# Sheet4.net
KiCad netlist of a schematic drawn in Altium Designer
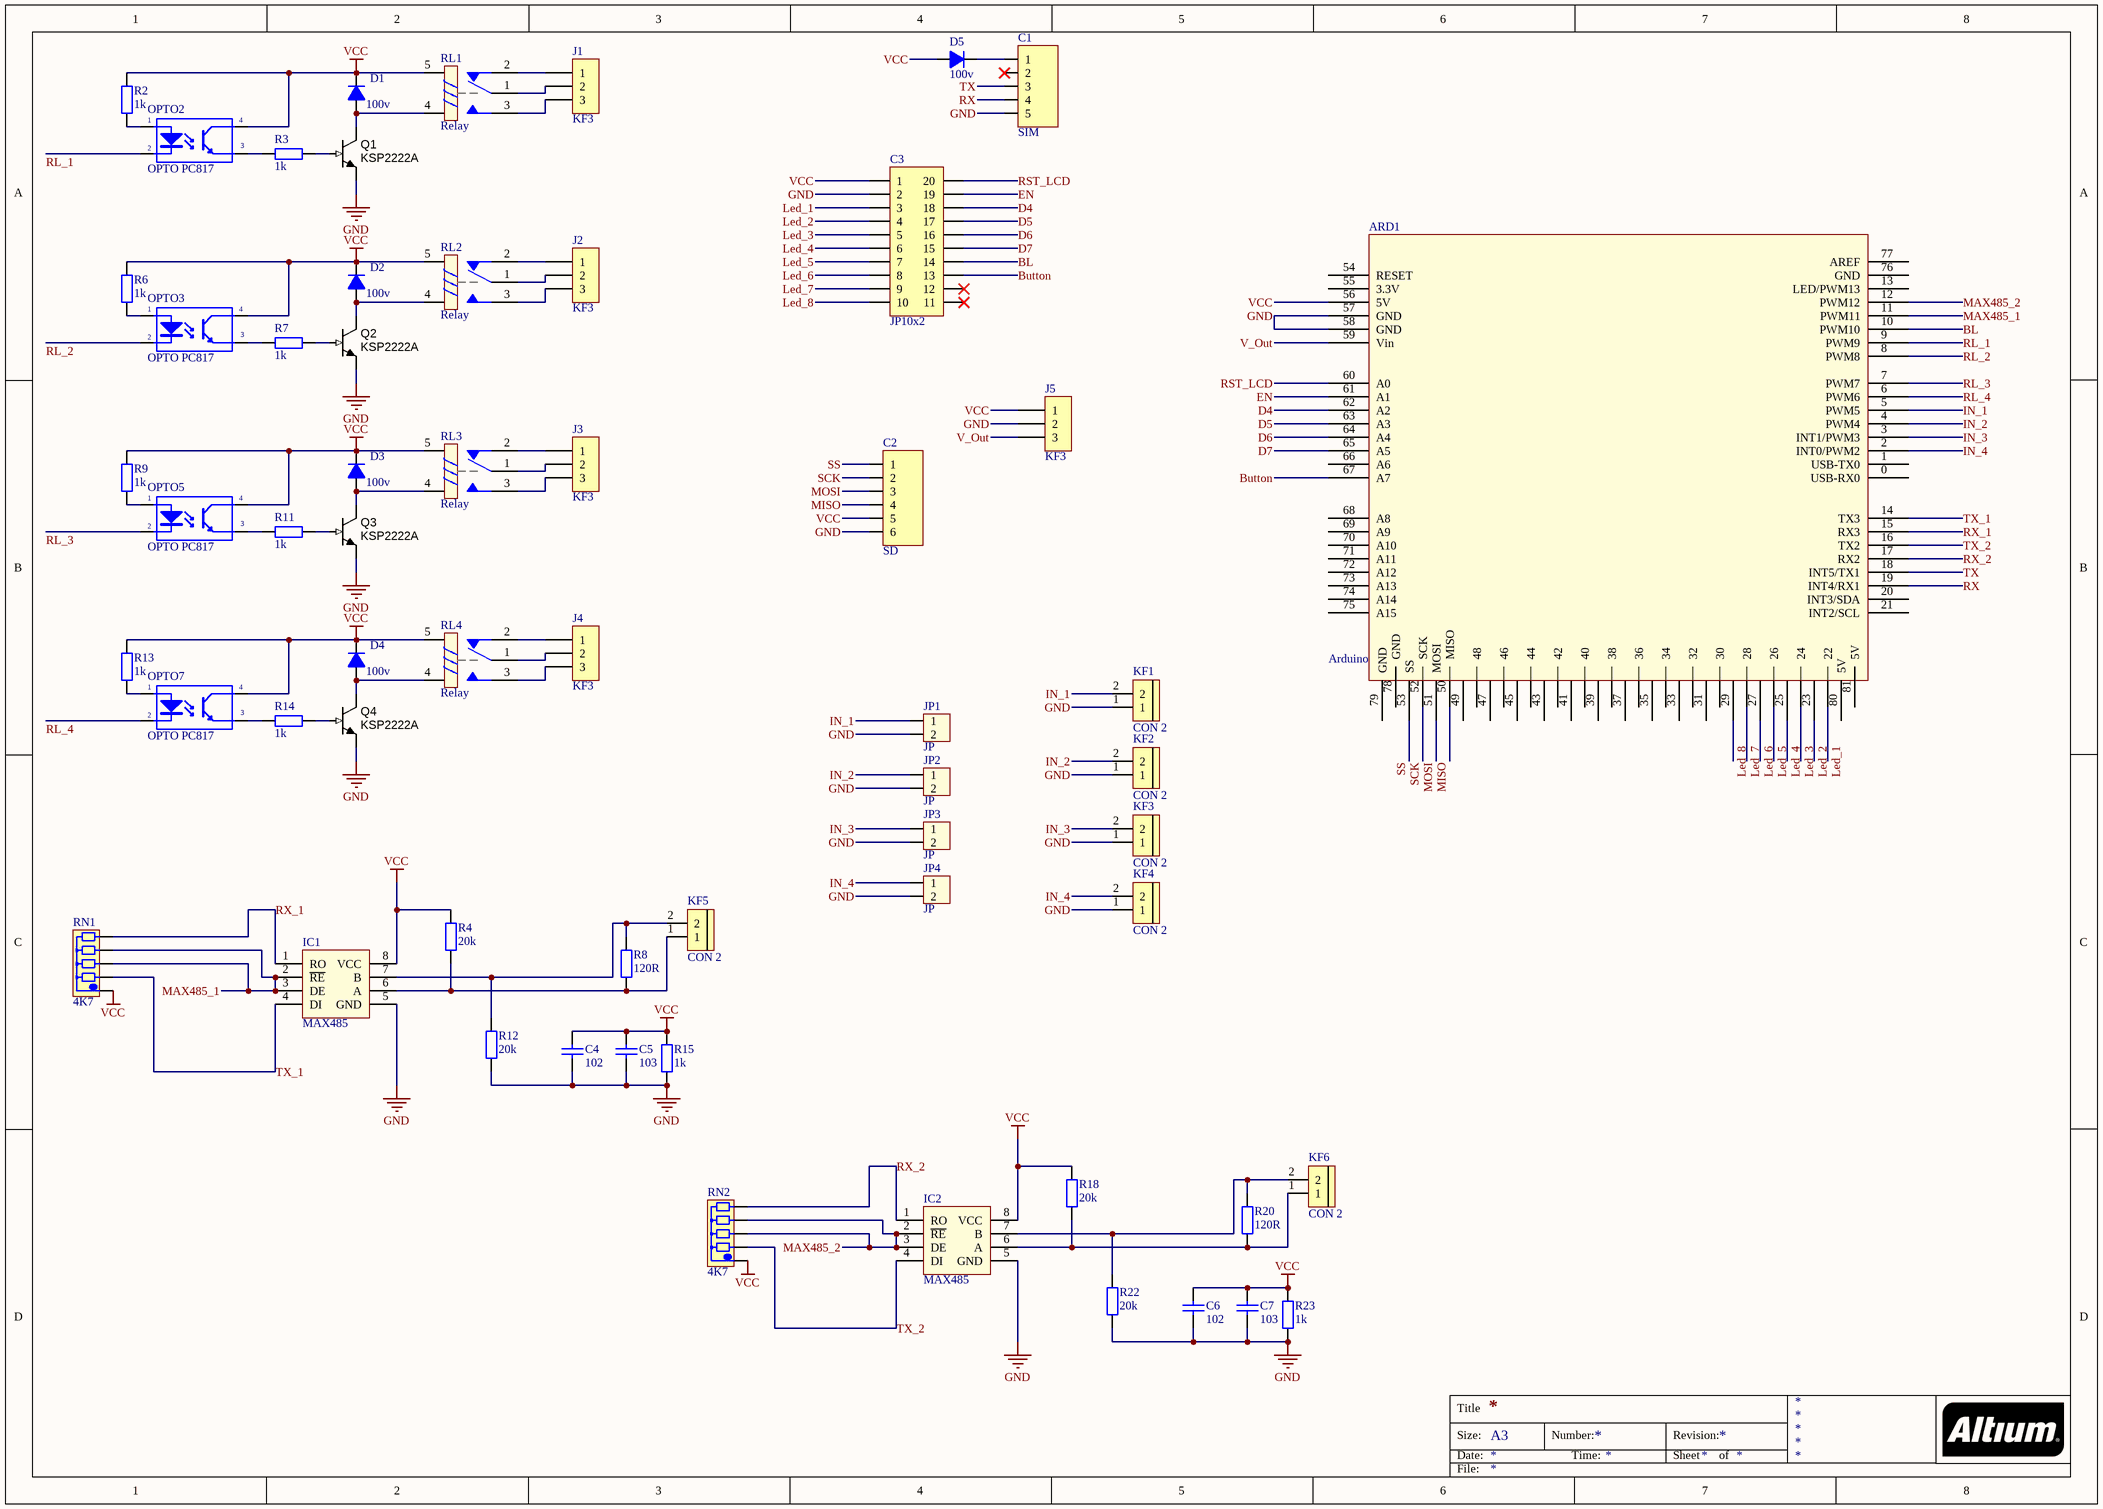
[diagram p0: Sheet4.SchDoc]

(export (version "E")
  (design (tool "Eeschema 10.0.6"))
  (components
    (comp (ref "ARD1") (value "Arduino") (footprint "Arduino") (libsource (lib "Arduino") (part "Arduino")))
    (comp (ref "C1")
      (value "SIM")
      (footprint "JP5-C1T")
      (description "WR-PHD 2.54 mm Angled Socket Header")
      (fields
        (field (name "MANUFACTURER") "Würth Elektronik eiSos GmbH")
        (field (name "PARTNO") "613005143121")
        (field (name "CREATED BY") "Karrer Zheng")
      )
      (libsource (lib "LIBRARY") (part "JP5"))
    )
    (comp (ref "C2")
      (value "SD")
      (footprint "JP6-C1T")
      (description "WR-PHD 2.54 mm Angled Socket Header")
      (fields
        (field (name "MANUFACTURER") "Würth Elektronik eiSos GmbH")
        (field (name "PARTNO") "613006143121")
        (field (name "CREATED BY") "Karrer Zheng")
      )
      (libsource (lib "LIBRARY") (part "JP6"))
    )
    (comp (ref "C3")
      (value "JP10x2")
      (footprint "JP10-C2T")
      (description "WR-PHD 2.54 mm Dual Socket Header")
      (fields
        (field (name "MANUFACTURER") "Würth Elektronik eiSos GmbH")
        (field (name "PARTNO") "61302021821")
        (field (name "CREATED BY") "Karrer Zheng")
      )
      (libsource (lib "LIBRARY") (part "JP10x2"))
    )
    (comp (ref "C4")
      (value "102")
      (footprint "tu gom")
      (description "Cắm")
      (libsource (lib "Altium_Lib_by_KhueNguyenCreator") (part "Tu gom 102 50V"))
    )
    (comp (ref "C5")
      (value "103")
      (footprint "tu gom")
      (description "Cắm")
      (libsource (lib "Altium_Lib_by_KhueNguyenCreator") (part "Tu gom 103 50V"))
    )
    (comp (ref "C6")
      (value "102")
      (footprint "tu gom")
      (description "Cắm")
      (libsource (lib "Altium_Lib_by_KhueNguyenCreator") (part "Tu gom 102 50V"))
    )
    (comp (ref "C7")
      (value "103")
      (footprint "tu gom")
      (description "Cắm")
      (libsource (lib "Altium_Lib_by_KhueNguyenCreator") (part "Tu gom 103 50V"))
    )
    (comp (ref "D1")
      (value "100v")
      (footprint "DIODE 1A")
      (description "Cắm")
      (libsource (lib "Altium_Lib_by_KhueNguyenCreator") (part "Diode 1N4007"))
    )
    (comp (ref "D2")
      (value "100v")
      (footprint "DIODE 1A")
      (description "Cắm")
      (libsource (lib "Altium_Lib_by_KhueNguyenCreator") (part "Diode 1N4007"))
    )
    (comp (ref "D3")
      (value "100v")
      (footprint "DIODE 1A")
      (description "Cắm")
      (libsource (lib "Altium_Lib_by_KhueNguyenCreator") (part "Diode 1N4007"))
    )
    (comp (ref "D4")
      (value "100v")
      (footprint "DIODE 1A")
      (description "Cắm")
      (libsource (lib "Altium_Lib_by_KhueNguyenCreator") (part "Diode 1N4007"))
    )
    (comp (ref "D5")
      (value "100v")
      (footprint "DIODE 1A")
      (description "Cắm")
      (libsource (lib "Altium_Lib_by_KhueNguyenCreator") (part "Diode 1N4007"))
    )
    (comp (ref "IC1")
      (value "MAX485")
      (footprint "DIP8/W0.3")
      (description "RS232 - RS485 (Same sn75176)")
      (libsource (lib "My Library") (part "MAX485"))
    )
    (comp (ref "IC2")
      (value "MAX485")
      (footprint "DIP8/W0.3")
      (description "RS232 - RS485 (Same sn75176)")
      (libsource (lib "My Library") (part "MAX485"))
    )
    (comp (ref "J1")
      (value "KF3")
      (footprint "KF3-5.08")
      (fields
        (field (name "MANUFACTURER") "Würth Elektronik eiSos GmbH")
        (field (name "PARTNO") "691103110003")
        (field (name "CREATED BY") "Karrer Zheng")
      )
      (libsource (lib "My Library") (part "KF3"))
    )
    (comp (ref "J2")
      (value "KF3")
      (footprint "KF3-5.08")
      (fields
        (field (name "MANUFACTURER") "Würth Elektronik eiSos GmbH")
        (field (name "PARTNO") "691103110003")
        (field (name "CREATED BY") "Karrer Zheng")
      )
      (libsource (lib "My Library") (part "KF3"))
    )
    (comp (ref "J3")
      (value "KF3")
      (footprint "KF3-5.08")
      (fields
        (field (name "MANUFACTURER") "Würth Elektronik eiSos GmbH")
        (field (name "PARTNO") "691103110003")
        (field (name "CREATED BY") "Karrer Zheng")
      )
      (libsource (lib "My Library") (part "KF3"))
    )
    (comp (ref "J4")
      (value "KF3")
      (footprint "KF3-5.08")
      (fields
        (field (name "MANUFACTURER") "Würth Elektronik eiSos GmbH")
        (field (name "PARTNO") "691103110003")
        (field (name "CREATED BY") "Karrer Zheng")
      )
      (libsource (lib "My Library") (part "KF3"))
    )
    (comp (ref "J5")
      (value "KF3")
      (footprint "KF3-5.08")
      (fields
        (field (name "MANUFACTURER") "Würth Elektronik eiSos GmbH")
        (field (name "PARTNO") "691103110003")
        (field (name "CREATED BY") "Karrer Zheng")
      )
      (libsource (lib "My Library") (part "KF3"))
    )
    (comp (ref "JP1")
      (value "JP")
      (footprint "jam2")
      (description "jam 2")
      (libsource (lib "My_Library_Altium") (part "Jam 2"))
    )
    (comp (ref "JP2")
      (value "JP")
      (footprint "jam2")
      (description "jam 2")
      (libsource (lib "My_Library_Altium") (part "Jam 2"))
    )
    (comp (ref "JP3")
      (value "JP")
      (footprint "jam2")
      (description "jam 2")
      (libsource (lib "My_Library_Altium") (part "Jam 2"))
    )
    (comp (ref "JP4")
      (value "JP")
      (footprint "jam2")
      (description "jam 2")
      (libsource (lib "My_Library_Altium") (part "Jam 2"))
    )
    (comp (ref "KF1")
      (value "CON 2")
      (footprint "Con 2 KF301 5.08")
      (description "Cắm")
      (libsource (lib "Altium_Lib_by_KhueNguyenCreator") (part "CON 2 KF301"))
    )
    (comp (ref "KF2")
      (value "CON 2")
      (footprint "Con 2 KF301 5.08")
      (description "Cắm")
      (libsource (lib "Altium_Lib_by_KhueNguyenCreator") (part "CON 2 KF301"))
    )
    (comp (ref "KF3")
      (value "CON 2")
      (footprint "Con 2 KF301 5.08")
      (description "Cắm")
      (libsource (lib "Altium_Lib_by_KhueNguyenCreator") (part "CON 2 KF301"))
    )
    (comp (ref "KF4")
      (value "CON 2")
      (footprint "Con 2 KF301 5.08")
      (description "Cắm")
      (libsource (lib "Altium_Lib_by_KhueNguyenCreator") (part "CON 2 KF301"))
    )
    (comp (ref "KF5")
      (value "CON 2")
      (footprint "Con 2 KF301 5.08")
      (description "Cắm")
      (libsource (lib "Altium_Lib_by_KhueNguyenCreator") (part "CON 2 KF301"))
    )
    (comp (ref "KF6")
      (value "CON 2")
      (footprint "Con 2 KF301 5.08")
      (description "Cắm")
      (libsource (lib "Altium_Lib_by_KhueNguyenCreator") (part "CON 2 KF301"))
    )
    (comp (ref "OPTO2")
      (value "OPTO PC817")
      (footprint "DIP4/W0.3")
      (description "Single Opto")
      (libsource (lib "My_Library_Altium") (part "OPTO PC817"))
    )
    (comp (ref "OPTO3")
      (value "OPTO PC817")
      (footprint "DIP4/W0.3")
      (description "Single Opto")
      (libsource (lib "My_Library_Altium") (part "OPTO PC817"))
    )
    (comp (ref "OPTO5")
      (value "OPTO PC817")
      (footprint "DIP4/W0.3")
      (description "Single Opto")
      (libsource (lib "My_Library_Altium") (part "OPTO PC817"))
    )
    (comp (ref "OPTO7")
      (value "OPTO PC817")
      (footprint "DIP4/W0.3")
      (description "Single Opto")
      (libsource (lib "My_Library_Altium") (part "OPTO PC817"))
    )
    (comp (ref "Q1")
      (value "KSP2222A")
      (footprint "TO-92_Flat")
      (description "Transistor SMD NPN 40V 0.6A 625mW TO-92")
      (libsource (lib "My_Library_Altium") (part "NPN_KSP2222A"))
    )
    (comp (ref "Q2")
      (value "KSP2222A")
      (footprint "TO-92_Flat")
      (description "Transistor SMD NPN 40V 0.6A 625mW TO-92")
      (libsource (lib "My_Library_Altium") (part "NPN_KSP2222A"))
    )
    (comp (ref "Q3")
      (value "KSP2222A")
      (footprint "TO-92_Flat")
      (description "Transistor SMD NPN 40V 0.6A 625mW TO-92")
      (libsource (lib "My_Library_Altium") (part "NPN_KSP2222A"))
    )
    (comp (ref "Q4")
      (value "KSP2222A")
      (footprint "TO-92_Flat")
      (description "Transistor SMD NPN 40V 0.6A 625mW TO-92")
      (libsource (lib "My_Library_Altium") (part "NPN_KSP2222A"))
    )
    (comp (ref "R2")
      (value "1k")
      (footprint "tro vach 1/2w")
      (description "Cắm")
      (libsource (lib "Altium_Lib_by_KhueNguyenCreator") (part "Tro Vach 1/2W 5% 1k"))
    )
    (comp (ref "R3")
      (value "1k")
      (footprint "tro vach 1/2w")
      (description "Cắm")
      (libsource (lib "Altium_Lib_by_KhueNguyenCreator") (part "Tro Vach 1/2W 5% 1k"))
    )
    (comp (ref "R4")
      (value "20k")
      (footprint "tro vach 1/4w")
      (description "Cắm")
      (libsource (lib "Altium_Lib_by_KhueNguyenCreator") (part "Tro Vach 1/4W 5% 20k"))
    )
    (comp (ref "R6")
      (value "1k")
      (footprint "tro vach 1/2w")
      (description "Cắm")
      (libsource (lib "Altium_Lib_by_KhueNguyenCreator") (part "Tro Vach 1/2W 5% 1k"))
    )
    (comp (ref "R7")
      (value "1k")
      (footprint "tro vach 1/2w")
      (description "Cắm")
      (libsource (lib "Altium_Lib_by_KhueNguyenCreator") (part "Tro Vach 1/2W 5% 1k"))
    )
    (comp (ref "R8")
      (value "120R")
      (footprint "tro vach 1/4w")
      (description "Cắm")
      (libsource (lib "Altium_Lib_by_KhueNguyenCreator") (part "Tro Vach 1/4W 5% 120R"))
    )
    (comp (ref "R9")
      (value "1k")
      (footprint "tro vach 1/2w")
      (description "Cắm")
      (libsource (lib "Altium_Lib_by_KhueNguyenCreator") (part "Tro Vach 1/2W 5% 1k"))
    )
    (comp (ref "R11")
      (value "1k")
      (footprint "tro vach 1/2w")
      (description "Cắm")
      (libsource (lib "Altium_Lib_by_KhueNguyenCreator") (part "Tro Vach 1/2W 5% 1k"))
    )
    (comp (ref "R12")
      (value "20k")
      (footprint "tro vach 1/4w")
      (description "Cắm")
      (libsource (lib "Altium_Lib_by_KhueNguyenCreator") (part "Tro Vach 1/4W 5% 20k"))
    )
    (comp (ref "R13")
      (value "1k")
      (footprint "tro vach 1/2w")
      (description "Cắm")
      (libsource (lib "Altium_Lib_by_KhueNguyenCreator") (part "Tro Vach 1/2W 5% 1k"))
    )
    (comp (ref "R14")
      (value "1k")
      (footprint "tro vach 1/2w")
      (description "Cắm")
      (libsource (lib "Altium_Lib_by_KhueNguyenCreator") (part "Tro Vach 1/2W 5% 1k"))
    )
    (comp (ref "R15")
      (value "1k")
      (footprint "tro vach 1/4w")
      (description "Cắm")
      (libsource (lib "Altium_Lib_by_KhueNguyenCreator") (part "Tro Vach 1/4W 5% 1k"))
    )
    (comp (ref "R18")
      (value "20k")
      (footprint "tro vach 1/4w")
      (description "Cắm")
      (libsource (lib "Altium_Lib_by_KhueNguyenCreator") (part "Tro Vach 1/4W 5% 20k"))
    )
    (comp (ref "R20")
      (value "120R")
      (footprint "tro vach 1/4w")
      (description "Cắm")
      (libsource (lib "Altium_Lib_by_KhueNguyenCreator") (part "Tro Vach 1/4W 5% 120R"))
    )
    (comp (ref "R22")
      (value "20k")
      (footprint "tro vach 1/4w")
      (description "Cắm")
      (libsource (lib "Altium_Lib_by_KhueNguyenCreator") (part "Tro Vach 1/4W 5% 20k"))
    )
    (comp (ref "R23")
      (value "1k")
      (footprint "tro vach 1/4w")
      (description "Cắm")
      (libsource (lib "Altium_Lib_by_KhueNguyenCreator") (part "Tro Vach 1/4W 5% 1k"))
    )
    (comp (ref "RL1")
      (value "Relay")
      (footprint "Relay 5 Chan SRD")
      (description "Relay 5 Chan")
      (libsource (lib "Altium_Lib_by_KhueNguyenCreator") (part "Relay 5 Chan SRD"))
    )
    (comp (ref "RL2")
      (value "Relay")
      (footprint "Relay 5 Chan SRD")
      (description "Relay 5 Chan")
      (libsource (lib "Altium_Lib_by_KhueNguyenCreator") (part "Relay 5 Chan SRD"))
    )
    (comp (ref "RL3")
      (value "Relay")
      (footprint "Relay 5 Chan SRD")
      (description "Relay 5 Chan")
      (libsource (lib "Altium_Lib_by_KhueNguyenCreator") (part "Relay 5 Chan SRD"))
    )
    (comp (ref "RL4")
      (value "Relay")
      (footprint "Relay 5 Chan SRD")
      (description "Relay 5 Chan")
      (libsource (lib "Altium_Lib_by_KhueNguyenCreator") (part "Relay 5 Chan SRD"))
    )
    (comp (ref "RN1")
      (value "4K7")
      (footprint "RN4")
      (description "Resistor 4 (thanh)")
      (libsource (lib "Cty1") (part "RN4"))
    )
    (comp (ref "RN2")
      (value "4K7")
      (footprint "RN4")
      (description "Resistor 4 (thanh)")
      (libsource (lib "Cty1") (part "RN4"))
    )
  )
  (nets
    (net (code "1") (name "/BL") (class "Default")
      (node (ref "ARD1") (pin "10") (pinfunction "PWM10_10") (pintype "passive"))
      (node (ref "C3") (pin "14") (pinfunction "14_14") (pintype "passive"))
    )
    (net (code "2") (name "/Button") (class "Default")
      (node (ref "ARD1") (pin "67") (pinfunction "A7_67") (pintype "passive"))
      (node (ref "C3") (pin "13") (pinfunction "13_13") (pintype "passive"))
    )
    (net (code "3") (name "/D4") (class "Default")
      (node (ref "ARD1") (pin "62") (pinfunction "A2_62") (pintype "passive"))
      (node (ref "C3") (pin "18") (pinfunction "18_18") (pintype "passive"))
    )
    (net (code "4") (name "/D5") (class "Default")
      (node (ref "ARD1") (pin "63") (pinfunction "A3_63") (pintype "passive"))
      (node (ref "C3") (pin "17") (pinfunction "17_17") (pintype "passive"))
    )
    (net (code "5") (name "/D6") (class "Default")
      (node (ref "ARD1") (pin "64") (pinfunction "A4_64") (pintype "passive"))
      (node (ref "C3") (pin "16") (pinfunction "16_16") (pintype "passive"))
    )
    (net (code "6") (name "/D7") (class "Default")
      (node (ref "ARD1") (pin "65") (pinfunction "A5_65") (pintype "passive"))
      (node (ref "C3") (pin "15") (pinfunction "15_15") (pintype "passive"))
    )
    (net (code "7") (name "/EN") (class "Default")
      (node (ref "ARD1") (pin "61") (pinfunction "A1_61") (pintype "passive"))
      (node (ref "C3") (pin "19") (pinfunction "19_19") (pintype "passive"))
    )
    (net (code "8") (name "/IN_1") (class "Default")
      (node (ref "ARD1") (pin "5") (pinfunction "PWM5_5") (pintype "passive"))
      (node (ref "JP1") (pin "1") (pinfunction "1_1") (pintype "passive"))
      (node (ref "KF1") (pin "2") (pinfunction "2_2") (pintype "passive"))
    )
    (net (code "9") (name "/IN_2") (class "Default")
      (node (ref "ARD1") (pin "4") (pinfunction "PWM4_4") (pintype "passive"))
      (node (ref "JP2") (pin "1") (pinfunction "1_1") (pintype "passive"))
      (node (ref "KF2") (pin "2") (pinfunction "2_2") (pintype "passive"))
    )
    (net (code "10") (name "/IN_3") (class "Default")
      (node (ref "ARD1") (pin "3") (pinfunction "INT1/PWM3_3") (pintype "passive"))
      (node (ref "JP3") (pin "1") (pinfunction "1_1") (pintype "passive"))
      (node (ref "KF3") (pin "2") (pinfunction "2_2") (pintype "passive"))
    )
    (net (code "11") (name "/IN_4") (class "Default")
      (node (ref "ARD1") (pin "2") (pinfunction "INT0/PWM2_2") (pintype "passive"))
      (node (ref "JP4") (pin "1") (pinfunction "1_1") (pintype "passive"))
      (node (ref "KF4") (pin "2") (pinfunction "2_2") (pintype "passive"))
    )
    (net (code "12") (name "/Led_1") (class "Default")
      (node (ref "ARD1") (pin "22") (pinfunction "22_22") (pintype "passive"))
      (node (ref "C3") (pin "3") (pinfunction "3_3") (pintype "passive"))
    )
    (net (code "13") (name "/Led_2") (class "Default")
      (node (ref "ARD1") (pin "23") (pinfunction "23_23") (pintype "passive"))
      (node (ref "C3") (pin "4") (pinfunction "4_4") (pintype "passive"))
    )
    (net (code "14") (name "/Led_3") (class "Default")
      (node (ref "ARD1") (pin "24") (pinfunction "24_24") (pintype "passive"))
      (node (ref "C3") (pin "5") (pinfunction "5_5") (pintype "passive"))
    )
    (net (code "15") (name "/Led_4") (class "Default")
      (node (ref "ARD1") (pin "25") (pinfunction "25_25") (pintype "passive"))
      (node (ref "C3") (pin "6") (pinfunction "6_6") (pintype "passive"))
    )
    (net (code "16") (name "/Led_5") (class "Default")
      (node (ref "ARD1") (pin "26") (pinfunction "26_26") (pintype "passive"))
      (node (ref "C3") (pin "7") (pinfunction "7_7") (pintype "passive"))
    )
    (net (code "17") (name "/Led_6") (class "Default")
      (node (ref "ARD1") (pin "27") (pinfunction "27_27") (pintype "passive"))
      (node (ref "C3") (pin "8") (pinfunction "8_8") (pintype "passive"))
    )
    (net (code "18") (name "/Led_7") (class "Default")
      (node (ref "ARD1") (pin "28") (pinfunction "28_28") (pintype "passive"))
      (node (ref "C3") (pin "9") (pinfunction "9_9") (pintype "passive"))
    )
    (net (code "19") (name "/Led_8") (class "Default")
      (node (ref "ARD1") (pin "29") (pinfunction "29_29") (pintype "passive"))
      (node (ref "C3") (pin "10") (pinfunction "10_10") (pintype "passive"))
    )
    (net (code "20") (name "/MAX485_1") (class "Default")
      (node (ref "ARD1") (pin "11") (pinfunction "PWM11_11") (pintype "passive"))
      (node (ref "IC1") (pin "2") (pinfunction "~{RE}_2") (pintype "passive"))
      (node (ref "IC1") (pin "3") (pinfunction "DE_3") (pintype "passive"))
      (node (ref "RN1") (pin "3") (pinfunction "3_3") (pintype "passive"))
      (node (ref "RN1") (pin "4") (pinfunction "4_4") (pintype "passive"))
    )
    (net (code "21") (name "/MAX485_2") (class "Default")
      (node (ref "ARD1") (pin "12") (pinfunction "PWM12_12") (pintype "passive"))
      (node (ref "IC2") (pin "2") (pinfunction "~{RE}_2") (pintype "passive"))
      (node (ref "IC2") (pin "3") (pinfunction "DE_3") (pintype "passive"))
      (node (ref "RN2") (pin "3") (pinfunction "3_3") (pintype "passive"))
      (node (ref "RN2") (pin "4") (pinfunction "4_4") (pintype "passive"))
    )
    (net (code "22") (name "/MISO") (class "Default")
      (node (ref "ARD1") (pin "50") (pinfunction "MISO_50") (pintype "passive"))
      (node (ref "C2") (pin "4") (pinfunction "4_4") (pintype "passive"))
    )
    (net (code "23") (name "/MOSI") (class "Default")
      (node (ref "ARD1") (pin "51") (pinfunction "MOSI_51") (pintype "passive"))
      (node (ref "C2") (pin "3") (pinfunction "3_3") (pintype "passive"))
    )
    (net (code "24") (name "/RL_1") (class "Default")
      (node (ref "ARD1") (pin "9") (pinfunction "PWM9_9") (pintype "passive"))
      (node (ref "OPTO2") (pin "2") (pinfunction "K_2") (pintype "passive"))
    )
    (net (code "25") (name "/RL_2") (class "Default")
      (node (ref "ARD1") (pin "8") (pinfunction "PWM8_8") (pintype "passive"))
      (node (ref "OPTO3") (pin "2") (pinfunction "K_2") (pintype "passive"))
    )
    (net (code "26") (name "/RL_3") (class "Default")
      (node (ref "ARD1") (pin "7") (pinfunction "PWM7_7") (pintype "passive"))
      (node (ref "OPTO5") (pin "2") (pinfunction "K_2") (pintype "passive"))
    )
    (net (code "27") (name "/RL_4") (class "Default")
      (node (ref "ARD1") (pin "6") (pinfunction "PWM6_6") (pintype "passive"))
      (node (ref "OPTO7") (pin "2") (pinfunction "K_2") (pintype "passive"))
    )
    (net (code "28") (name "/RST_LCD") (class "Default")
      (node (ref "ARD1") (pin "60") (pinfunction "A0_60") (pintype "passive"))
      (node (ref "C3") (pin "20") (pinfunction "20_20") (pintype "passive"))
    )
    (net (code "29") (name "/RX") (class "Default")
      (node (ref "ARD1") (pin "19") (pinfunction "INT4/RX1_19") (pintype "passive"))
      (node (ref "C1") (pin "4") (pinfunction "4_4") (pintype "passive"))
    )
    (net (code "30") (name "/RX_1") (class "Default")
      (node (ref "ARD1") (pin "15") (pinfunction "RX3_15") (pintype "passive"))
      (node (ref "IC1") (pin "1") (pinfunction "RO_1") (pintype "passive"))
      (node (ref "RN1") (pin "5") (pinfunction "5_5") (pintype "passive"))
    )
    (net (code "31") (name "/RX_2") (class "Default")
      (node (ref "ARD1") (pin "17") (pinfunction "RX2_17") (pintype "passive"))
      (node (ref "IC2") (pin "1") (pinfunction "RO_1") (pintype "passive"))
      (node (ref "RN2") (pin "5") (pinfunction "5_5") (pintype "passive"))
    )
    (net (code "32") (name "/SCK") (class "Default")
      (node (ref "ARD1") (pin "52") (pinfunction "SCK_52") (pintype "passive"))
      (node (ref "C2") (pin "2") (pinfunction "2_2") (pintype "passive"))
    )
    (net (code "33") (name "/SS") (class "Default")
      (node (ref "ARD1") (pin "53") (pinfunction "SS_53") (pintype "passive"))
      (node (ref "C2") (pin "1") (pinfunction "1_1") (pintype "passive"))
    )
    (net (code "34") (name "/TX") (class "Default")
      (node (ref "ARD1") (pin "18") (pinfunction "INT5/TX1_18") (pintype "passive"))
      (node (ref "C1") (pin "3") (pinfunction "3_3") (pintype "passive"))
    )
    (net (code "35") (name "/TX_1") (class "Default")
      (node (ref "ARD1") (pin "14") (pinfunction "TX3_14") (pintype "passive"))
      (node (ref "IC1") (pin "4") (pinfunction "DI_4") (pintype "passive"))
      (node (ref "RN1") (pin "2") (pinfunction "2_2") (pintype "passive"))
    )
    (net (code "36") (name "/TX_2") (class "Default")
      (node (ref "ARD1") (pin "16") (pinfunction "TX2_16") (pintype "passive"))
      (node (ref "IC2") (pin "4") (pinfunction "DI_4") (pintype "passive"))
      (node (ref "RN2") (pin "2") (pinfunction "2_2") (pintype "passive"))
    )
    (net (code "37") (name "/V_Out") (class "Default")
      (node (ref "ARD1") (pin "59") (pinfunction "Vin_59") (pintype "passive"))
      (node (ref "J5") (pin "3") (pinfunction "3_3") (pintype "passive"))
    )
    (net (code "38") (name "GND") (class "Default")
      (node (ref "ARD1") (pin "57") (pinfunction "GND_57") (pintype "passive"))
      (node (ref "ARD1") (pin "58") (pinfunction "GND_58") (pintype "passive"))
      (node (ref "C1") (pin "5") (pinfunction "5_5") (pintype "passive"))
      (node (ref "C2") (pin "6") (pinfunction "6_6") (pintype "passive"))
      (node (ref "C3") (pin "2") (pinfunction "2_2") (pintype "passive"))
      (node (ref "C4") (pin "2") (pinfunction "2_2") (pintype "passive"))
      (node (ref "C5") (pin "2") (pinfunction "2_2") (pintype "passive"))
      (node (ref "C6") (pin "2") (pinfunction "2_2") (pintype "passive"))
      (node (ref "C7") (pin "2") (pinfunction "2_2") (pintype "passive"))
      (node (ref "IC1") (pin "5") (pinfunction "GND_5") (pintype "passive"))
      (node (ref "IC2") (pin "5") (pinfunction "GND_5") (pintype "passive"))
      (node (ref "J5") (pin "2") (pinfunction "2_2") (pintype "passive"))
      (node (ref "JP1") (pin "2") (pinfunction "2_2") (pintype "passive"))
      (node (ref "JP2") (pin "2") (pinfunction "2_2") (pintype "passive"))
      (node (ref "JP3") (pin "2") (pinfunction "2_2") (pintype "passive"))
      (node (ref "JP4") (pin "2") (pinfunction "2_2") (pintype "passive"))
      (node (ref "KF1") (pin "1") (pinfunction "1_1") (pintype "passive"))
      (node (ref "KF2") (pin "1") (pinfunction "1_1") (pintype "passive"))
      (node (ref "KF3") (pin "1") (pinfunction "1_1") (pintype "passive"))
      (node (ref "KF4") (pin "1") (pinfunction "1_1") (pintype "passive"))
      (node (ref "Q1") (pin "1") (pinfunction "E_1") (pintype "passive"))
      (node (ref "Q2") (pin "1") (pinfunction "E_1") (pintype "passive"))
      (node (ref "Q3") (pin "1") (pinfunction "E_1") (pintype "passive"))
      (node (ref "Q4") (pin "1") (pinfunction "E_1") (pintype "passive"))
      (node (ref "R12") (pin "1") (pinfunction "1_1") (pintype "passive"))
      (node (ref "R15") (pin "1") (pinfunction "1_1") (pintype "passive"))
      (node (ref "R22") (pin "1") (pinfunction "1_1") (pintype "passive"))
      (node (ref "R23") (pin "1") (pinfunction "1_1") (pintype "passive"))
    )
    (net (code "39") (name "Net-(D1-A)") (class "Default")
      (node (ref "D1") (pin "1") (pinfunction "A_1") (pintype "passive"))
      (node (ref "Q1") (pin "3") (pinfunction "C_3") (pintype "passive"))
      (node (ref "RL1") (pin "4") (pinfunction "4_4") (pintype "passive"))
    )
    (net (code "40") (name "Net-(D2-A)") (class "Default")
      (node (ref "D2") (pin "1") (pinfunction "A_1") (pintype "passive"))
      (node (ref "Q2") (pin "3") (pinfunction "C_3") (pintype "passive"))
      (node (ref "RL2") (pin "4") (pinfunction "4_4") (pintype "passive"))
    )
    (net (code "41") (name "Net-(D3-A)") (class "Default")
      (node (ref "D3") (pin "1") (pinfunction "A_1") (pintype "passive"))
      (node (ref "Q3") (pin "3") (pinfunction "C_3") (pintype "passive"))
      (node (ref "RL3") (pin "4") (pinfunction "4_4") (pintype "passive"))
    )
    (net (code "42") (name "Net-(D4-A)") (class "Default")
      (node (ref "D4") (pin "1") (pinfunction "A_1") (pintype "passive"))
      (node (ref "Q4") (pin "3") (pinfunction "C_3") (pintype "passive"))
      (node (ref "RL4") (pin "4") (pinfunction "4_4") (pintype "passive"))
    )
    (net (code "43") (name "Net-(D5-K)") (class "Default")
      (node (ref "C1") (pin "1") (pinfunction "1_1") (pintype "passive"))
      (node (ref "D5") (pin "2") (pinfunction "K_2") (pintype "passive"))
    )
    (net (code "44") (name "Net-(IC1-A)") (class "Default")
      (node (ref "IC1") (pin "6") (pinfunction "A_6") (pintype "passive"))
      (node (ref "KF5") (pin "1") (pinfunction "1_1") (pintype "passive"))
      (node (ref "R4") (pin "1") (pinfunction "1_1") (pintype "passive"))
      (node (ref "R8") (pin "1") (pinfunction "1_1") (pintype "passive"))
    )
    (net (code "45") (name "Net-(IC1-B)") (class "Default")
      (node (ref "IC1") (pin "7") (pinfunction "B_7") (pintype "passive"))
      (node (ref "KF5") (pin "2") (pinfunction "2_2") (pintype "passive"))
      (node (ref "R12") (pin "2") (pinfunction "2_2") (pintype "passive"))
      (node (ref "R8") (pin "2") (pinfunction "2_2") (pintype "passive"))
    )
    (net (code "46") (name "Net-(IC2-A)") (class "Default")
      (node (ref "IC2") (pin "6") (pinfunction "A_6") (pintype "passive"))
      (node (ref "KF6") (pin "1") (pinfunction "1_1") (pintype "passive"))
      (node (ref "R18") (pin "1") (pinfunction "1_1") (pintype "passive"))
      (node (ref "R20") (pin "1") (pinfunction "1_1") (pintype "passive"))
    )
    (net (code "47") (name "Net-(IC2-B)") (class "Default")
      (node (ref "IC2") (pin "7") (pinfunction "B_7") (pintype "passive"))
      (node (ref "KF6") (pin "2") (pinfunction "2_2") (pintype "passive"))
      (node (ref "R20") (pin "2") (pinfunction "2_2") (pintype "passive"))
      (node (ref "R22") (pin "2") (pinfunction "2_2") (pintype "passive"))
    )
    (net (code "48") (name "Net-(J1-Pad1)") (class "Default")
      (node (ref "J1") (pin "1") (pinfunction "1_1") (pintype "passive"))
      (node (ref "RL1") (pin "2") (pinfunction "2_2") (pintype "passive"))
    )
    (net (code "49") (name "Net-(J1-Pad2)") (class "Default")
      (node (ref "J1") (pin "2") (pinfunction "2_2") (pintype "passive"))
      (node (ref "RL1") (pin "1") (pinfunction "1_1") (pintype "passive"))
    )
    (net (code "50") (name "Net-(J1-Pad3)") (class "Default")
      (node (ref "J1") (pin "3") (pinfunction "3_3") (pintype "passive"))
      (node (ref "RL1") (pin "3") (pinfunction "3_3") (pintype "passive"))
    )
    (net (code "51") (name "Net-(J2-Pad1)") (class "Default")
      (node (ref "J2") (pin "1") (pinfunction "1_1") (pintype "passive"))
      (node (ref "RL2") (pin "2") (pinfunction "2_2") (pintype "passive"))
    )
    (net (code "52") (name "Net-(J2-Pad2)") (class "Default")
      (node (ref "J2") (pin "2") (pinfunction "2_2") (pintype "passive"))
      (node (ref "RL2") (pin "1") (pinfunction "1_1") (pintype "passive"))
    )
    (net (code "53") (name "Net-(J2-Pad3)") (class "Default")
      (node (ref "J2") (pin "3") (pinfunction "3_3") (pintype "passive"))
      (node (ref "RL2") (pin "3") (pinfunction "3_3") (pintype "passive"))
    )
    (net (code "54") (name "Net-(J3-Pad1)") (class "Default")
      (node (ref "J3") (pin "1") (pinfunction "1_1") (pintype "passive"))
      (node (ref "RL3") (pin "2") (pinfunction "2_2") (pintype "passive"))
    )
    (net (code "55") (name "Net-(J3-Pad2)") (class "Default")
      (node (ref "J3") (pin "2") (pinfunction "2_2") (pintype "passive"))
      (node (ref "RL3") (pin "1") (pinfunction "1_1") (pintype "passive"))
    )
    (net (code "56") (name "Net-(J3-Pad3)") (class "Default")
      (node (ref "J3") (pin "3") (pinfunction "3_3") (pintype "passive"))
      (node (ref "RL3") (pin "3") (pinfunction "3_3") (pintype "passive"))
    )
    (net (code "57") (name "Net-(J4-Pad1)") (class "Default")
      (node (ref "J4") (pin "1") (pinfunction "1_1") (pintype "passive"))
      (node (ref "RL4") (pin "2") (pinfunction "2_2") (pintype "passive"))
    )
    (net (code "58") (name "Net-(J4-Pad2)") (class "Default")
      (node (ref "J4") (pin "2") (pinfunction "2_2") (pintype "passive"))
      (node (ref "RL4") (pin "1") (pinfunction "1_1") (pintype "passive"))
    )
    (net (code "59") (name "Net-(J4-Pad3)") (class "Default")
      (node (ref "J4") (pin "3") (pinfunction "3_3") (pintype "passive"))
      (node (ref "RL4") (pin "3") (pinfunction "3_3") (pintype "passive"))
    )
    (net (code "60") (name "Net-(OPTO2-A)") (class "Default")
      (node (ref "OPTO2") (pin "1") (pinfunction "A_1") (pintype "passive"))
      (node (ref "R2") (pin "1") (pinfunction "1_1") (pintype "passive"))
    )
    (net (code "61") (name "Net-(OPTO2-E)") (class "Default")
      (node (ref "OPTO2") (pin "3") (pinfunction "E_3") (pintype "passive"))
      (node (ref "R3") (pin "1") (pinfunction "1_1") (pintype "passive"))
    )
    (net (code "62") (name "Net-(OPTO3-A)") (class "Default")
      (node (ref "OPTO3") (pin "1") (pinfunction "A_1") (pintype "passive"))
      (node (ref "R6") (pin "1") (pinfunction "1_1") (pintype "passive"))
    )
    (net (code "63") (name "Net-(OPTO3-E)") (class "Default")
      (node (ref "OPTO3") (pin "3") (pinfunction "E_3") (pintype "passive"))
      (node (ref "R7") (pin "1") (pinfunction "1_1") (pintype "passive"))
    )
    (net (code "64") (name "Net-(OPTO5-A)") (class "Default")
      (node (ref "OPTO5") (pin "1") (pinfunction "A_1") (pintype "passive"))
      (node (ref "R9") (pin "1") (pinfunction "1_1") (pintype "passive"))
    )
    (net (code "65") (name "Net-(OPTO5-E)") (class "Default")
      (node (ref "OPTO5") (pin "3") (pinfunction "E_3") (pintype "passive"))
      (node (ref "R11") (pin "1") (pinfunction "1_1") (pintype "passive"))
    )
    (net (code "66") (name "Net-(OPTO7-A)") (class "Default")
      (node (ref "OPTO7") (pin "1") (pinfunction "A_1") (pintype "passive"))
      (node (ref "R13") (pin "1") (pinfunction "1_1") (pintype "passive"))
    )
    (net (code "67") (name "Net-(OPTO7-E)") (class "Default")
      (node (ref "OPTO7") (pin "3") (pinfunction "E_3") (pintype "passive"))
      (node (ref "R14") (pin "1") (pinfunction "1_1") (pintype "passive"))
    )
    (net (code "68") (name "Net-(Q1-B)") (class "Default")
      (node (ref "Q1") (pin "2") (pinfunction "B_2") (pintype "input"))
      (node (ref "R3") (pin "2") (pinfunction "2_2") (pintype "passive"))
    )
    (net (code "69") (name "Net-(Q2-B)") (class "Default")
      (node (ref "Q2") (pin "2") (pinfunction "B_2") (pintype "input"))
      (node (ref "R7") (pin "2") (pinfunction "2_2") (pintype "passive"))
    )
    (net (code "70") (name "Net-(Q3-B)") (class "Default")
      (node (ref "Q3") (pin "2") (pinfunction "B_2") (pintype "input"))
      (node (ref "R11") (pin "2") (pinfunction "2_2") (pintype "passive"))
    )
    (net (code "71") (name "Net-(Q4-B)") (class "Default")
      (node (ref "Q4") (pin "2") (pinfunction "B_2") (pintype "input"))
      (node (ref "R14") (pin "2") (pinfunction "2_2") (pintype "passive"))
    )
    (net (code "72") (name "VCC") (class "Default")
      (node (ref "ARD1") (pin "56") (pinfunction "5V_56") (pintype "passive"))
      (node (ref "C2") (pin "5") (pinfunction "5_5") (pintype "passive"))
      (node (ref "C3") (pin "1") (pinfunction "1_1") (pintype "passive"))
      (node (ref "C4") (pin "1") (pinfunction "1_1") (pintype "passive"))
      (node (ref "C5") (pin "1") (pinfunction "1_1") (pintype "passive"))
      (node (ref "C6") (pin "1") (pinfunction "1_1") (pintype "passive"))
      (node (ref "C7") (pin "1") (pinfunction "1_1") (pintype "passive"))
      (node (ref "D1") (pin "2") (pinfunction "K_2") (pintype "passive"))
      (node (ref "D2") (pin "2") (pinfunction "K_2") (pintype "passive"))
      (node (ref "D3") (pin "2") (pinfunction "K_2") (pintype "passive"))
      (node (ref "D4") (pin "2") (pinfunction "K_2") (pintype "passive"))
      (node (ref "D5") (pin "1") (pinfunction "A_1") (pintype "passive"))
      (node (ref "IC1") (pin "8") (pinfunction "VCC_8") (pintype "passive"))
      (node (ref "IC2") (pin "8") (pinfunction "VCC_8") (pintype "passive"))
      (node (ref "J5") (pin "1") (pinfunction "1_1") (pintype "passive"))
      (node (ref "OPTO2") (pin "4") (pinfunction "C_4") (pintype "passive"))
      (node (ref "OPTO3") (pin "4") (pinfunction "C_4") (pintype "passive"))
      (node (ref "OPTO5") (pin "4") (pinfunction "C_4") (pintype "passive"))
      (node (ref "OPTO7") (pin "4") (pinfunction "C_4") (pintype "passive"))
      (node (ref "R13") (pin "2") (pinfunction "2_2") (pintype "passive"))
      (node (ref "R15") (pin "2") (pinfunction "2_2") (pintype "passive"))
      (node (ref "R18") (pin "2") (pinfunction "2_2") (pintype "passive"))
      (node (ref "R2") (pin "2") (pinfunction "2_2") (pintype "passive"))
      (node (ref "R23") (pin "2") (pinfunction "2_2") (pintype "passive"))
      (node (ref "R4") (pin "2") (pinfunction "2_2") (pintype "passive"))
      (node (ref "R6") (pin "2") (pinfunction "2_2") (pintype "passive"))
      (node (ref "R9") (pin "2") (pinfunction "2_2") (pintype "passive"))
      (node (ref "RL1") (pin "5") (pinfunction "5_5") (pintype "passive"))
      (node (ref "RL2") (pin "5") (pinfunction "5_5") (pintype "passive"))
      (node (ref "RL3") (pin "5") (pinfunction "5_5") (pintype "passive"))
      (node (ref "RL4") (pin "5") (pinfunction "5_5") (pintype "passive"))
      (node (ref "RN1") (pin "1") (pinfunction "1_1") (pintype "passive"))
      (node (ref "RN2") (pin "1") (pinfunction "1_1") (pintype "passive"))
    )
    (net (code "73") (name "unconnected-(ARD1-3.3V-Pad55)") (class "Default")
      (node (ref "ARD1") (pin "55") (pinfunction "3.3V_55") (pintype "passive"))
    )
    (net (code "74") (name "unconnected-(ARD1-5V-Pad80)") (class "Default")
      (node (ref "ARD1") (pin "80") (pinfunction "5V_80") (pintype "passive"))
    )
    (net (code "75") (name "unconnected-(ARD1-5V-Pad81)") (class "Default")
      (node (ref "ARD1") (pin "81") (pinfunction "5V_81") (pintype "passive"))
    )
    (net (code "76") (name "unconnected-(ARD1-A6-Pad66)") (class "Default")
      (node (ref "ARD1") (pin "66") (pinfunction "A6_66") (pintype "passive"))
    )
    (net (code "77") (name "unconnected-(ARD1-A8-Pad68)") (class "Default")
      (node (ref "ARD1") (pin "68") (pinfunction "A8_68") (pintype "passive"))
    )
    (net (code "78") (name "unconnected-(ARD1-A9-Pad69)") (class "Default")
      (node (ref "ARD1") (pin "69") (pinfunction "A9_69") (pintype "passive"))
    )
    (net (code "79") (name "unconnected-(ARD1-A10-Pad70)") (class "Default")
      (node (ref "ARD1") (pin "70") (pinfunction "A10_70") (pintype "passive"))
    )
    (net (code "80") (name "unconnected-(ARD1-A11-Pad71)") (class "Default")
      (node (ref "ARD1") (pin "71") (pinfunction "A11_71") (pintype "passive"))
    )
    (net (code "81") (name "unconnected-(ARD1-A12-Pad72)") (class "Default")
      (node (ref "ARD1") (pin "72") (pinfunction "A12_72") (pintype "passive"))
    )
    (net (code "82") (name "unconnected-(ARD1-A13-Pad73)") (class "Default")
      (node (ref "ARD1") (pin "73") (pinfunction "A13_73") (pintype "passive"))
    )
    (net (code "83") (name "unconnected-(ARD1-A14-Pad74)") (class "Default")
      (node (ref "ARD1") (pin "74") (pinfunction "A14_74") (pintype "passive"))
    )
    (net (code "84") (name "unconnected-(ARD1-A15-Pad75)") (class "Default")
      (node (ref "ARD1") (pin "75") (pinfunction "A15_75") (pintype "passive"))
    )
    (net (code "85") (name "unconnected-(ARD1-AREF-Pad77)") (class "Default")
      (node (ref "ARD1") (pin "77") (pinfunction "AREF_77") (pintype "passive"))
    )
    (net (code "86") (name "unconnected-(ARD1-GND-Pad76)") (class "Default")
      (node (ref "ARD1") (pin "76") (pinfunction "GND_76") (pintype "passive"))
    )
    (net (code "87") (name "unconnected-(ARD1-GND-Pad78)") (class "Default")
      (node (ref "ARD1") (pin "78") (pinfunction "GND_78") (pintype "passive"))
    )
    (net (code "88") (name "unconnected-(ARD1-GND-Pad79)") (class "Default")
      (node (ref "ARD1") (pin "79") (pinfunction "GND_79") (pintype "passive"))
    )
    (net (code "89") (name "unconnected-(ARD1-INT2{slash}SCL-Pad21)") (class "Default")
      (node (ref "ARD1") (pin "21") (pinfunction "INT2/SCL_21") (pintype "passive"))
    )
    (net (code "90") (name "unconnected-(ARD1-INT3{slash}SDA-Pad20)") (class "Default")
      (node (ref "ARD1") (pin "20") (pinfunction "INT3/SDA_20") (pintype "passive"))
    )
    (net (code "91") (name "unconnected-(ARD1-LED{slash}PWM13-Pad13)") (class "Default")
      (node (ref "ARD1") (pin "13") (pinfunction "LED/PWM13_13") (pintype "passive"))
    )
    (net (code "92") (name "unconnected-(ARD1-Pad30)") (class "Default")
      (node (ref "ARD1") (pin "30") (pinfunction "30_30") (pintype "passive"))
    )
    (net (code "93") (name "unconnected-(ARD1-Pad31)") (class "Default")
      (node (ref "ARD1") (pin "31") (pinfunction "31_31") (pintype "passive"))
    )
    (net (code "94") (name "unconnected-(ARD1-Pad32)") (class "Default")
      (node (ref "ARD1") (pin "32") (pinfunction "32_32") (pintype "passive"))
    )
    (net (code "95") (name "unconnected-(ARD1-Pad33)") (class "Default")
      (node (ref "ARD1") (pin "33") (pinfunction "33_33") (pintype "passive"))
    )
    (net (code "96") (name "unconnected-(ARD1-Pad34)") (class "Default")
      (node (ref "ARD1") (pin "34") (pinfunction "34_34") (pintype "passive"))
    )
    (net (code "97") (name "unconnected-(ARD1-Pad35)") (class "Default")
      (node (ref "ARD1") (pin "35") (pinfunction "35_35") (pintype "passive"))
    )
    (net (code "98") (name "unconnected-(ARD1-Pad36)") (class "Default")
      (node (ref "ARD1") (pin "36") (pinfunction "36_36") (pintype "passive"))
    )
    (net (code "99") (name "unconnected-(ARD1-Pad37)") (class "Default")
      (node (ref "ARD1") (pin "37") (pinfunction "37_37") (pintype "passive"))
    )
    (net (code "100") (name "unconnected-(ARD1-Pad38)") (class "Default")
      (node (ref "ARD1") (pin "38") (pinfunction "38_38") (pintype "passive"))
    )
    (net (code "101") (name "unconnected-(ARD1-Pad39)") (class "Default")
      (node (ref "ARD1") (pin "39") (pinfunction "39_39") (pintype "passive"))
    )
    (net (code "102") (name "unconnected-(ARD1-Pad40)") (class "Default")
      (node (ref "ARD1") (pin "40") (pinfunction "40_40") (pintype "passive"))
    )
    (net (code "103") (name "unconnected-(ARD1-Pad41)") (class "Default")
      (node (ref "ARD1") (pin "41") (pinfunction "41_41") (pintype "passive"))
    )
    (net (code "104") (name "unconnected-(ARD1-Pad42)") (class "Default")
      (node (ref "ARD1") (pin "42") (pinfunction "42_42") (pintype "passive"))
    )
    (net (code "105") (name "unconnected-(ARD1-Pad43)") (class "Default")
      (node (ref "ARD1") (pin "43") (pinfunction "43_43") (pintype "passive"))
    )
    (net (code "106") (name "unconnected-(ARD1-Pad44)") (class "Default")
      (node (ref "ARD1") (pin "44") (pinfunction "44_44") (pintype "passive"))
    )
    (net (code "107") (name "unconnected-(ARD1-Pad45)") (class "Default")
      (node (ref "ARD1") (pin "45") (pinfunction "45_45") (pintype "passive"))
    )
    (net (code "108") (name "unconnected-(ARD1-Pad46)") (class "Default")
      (node (ref "ARD1") (pin "46") (pinfunction "46_46") (pintype "passive"))
    )
    (net (code "109") (name "unconnected-(ARD1-Pad47)") (class "Default")
      (node (ref "ARD1") (pin "47") (pinfunction "47_47") (pintype "passive"))
    )
    (net (code "110") (name "unconnected-(ARD1-Pad48)") (class "Default")
      (node (ref "ARD1") (pin "48") (pinfunction "48_48") (pintype "passive"))
    )
    (net (code "111") (name "unconnected-(ARD1-Pad49)") (class "Default")
      (node (ref "ARD1") (pin "49") (pinfunction "49_49") (pintype "passive"))
    )
    (net (code "112") (name "unconnected-(ARD1-RESET-Pad54)") (class "Default")
      (node (ref "ARD1") (pin "54") (pinfunction "RESET_54") (pintype "passive"))
    )
    (net (code "113") (name "unconnected-(ARD1-USB-RX0-Pad0)") (class "Default")
      (node (ref "ARD1") (pin "0") (pinfunction "USB-RX0_0") (pintype "passive"))
    )
    (net (code "114") (name "unconnected-(ARD1-USB-TX0-Pad1)") (class "Default")
      (node (ref "ARD1") (pin "1") (pinfunction "USB-TX0_1") (pintype "passive"))
    )
    (net (code "115") (name "unconnected-(C1-Pad2)") (class "Default")
      (node (ref "C1") (pin "2") (pinfunction "2_2") (pintype "passive+no_connect"))
    )
    (net (code "116") (name "unconnected-(C3-Pad11)") (class "Default")
      (node (ref "C3") (pin "11") (pinfunction "11_11") (pintype "passive+no_connect"))
    )
    (net (code "117") (name "unconnected-(C3-Pad12)") (class "Default")
      (node (ref "C3") (pin "12") (pinfunction "12_12") (pintype "passive+no_connect"))
    )
  )
)
